# MainBoard.net
KiCad netlist of a schematic drawn in Altium Designer
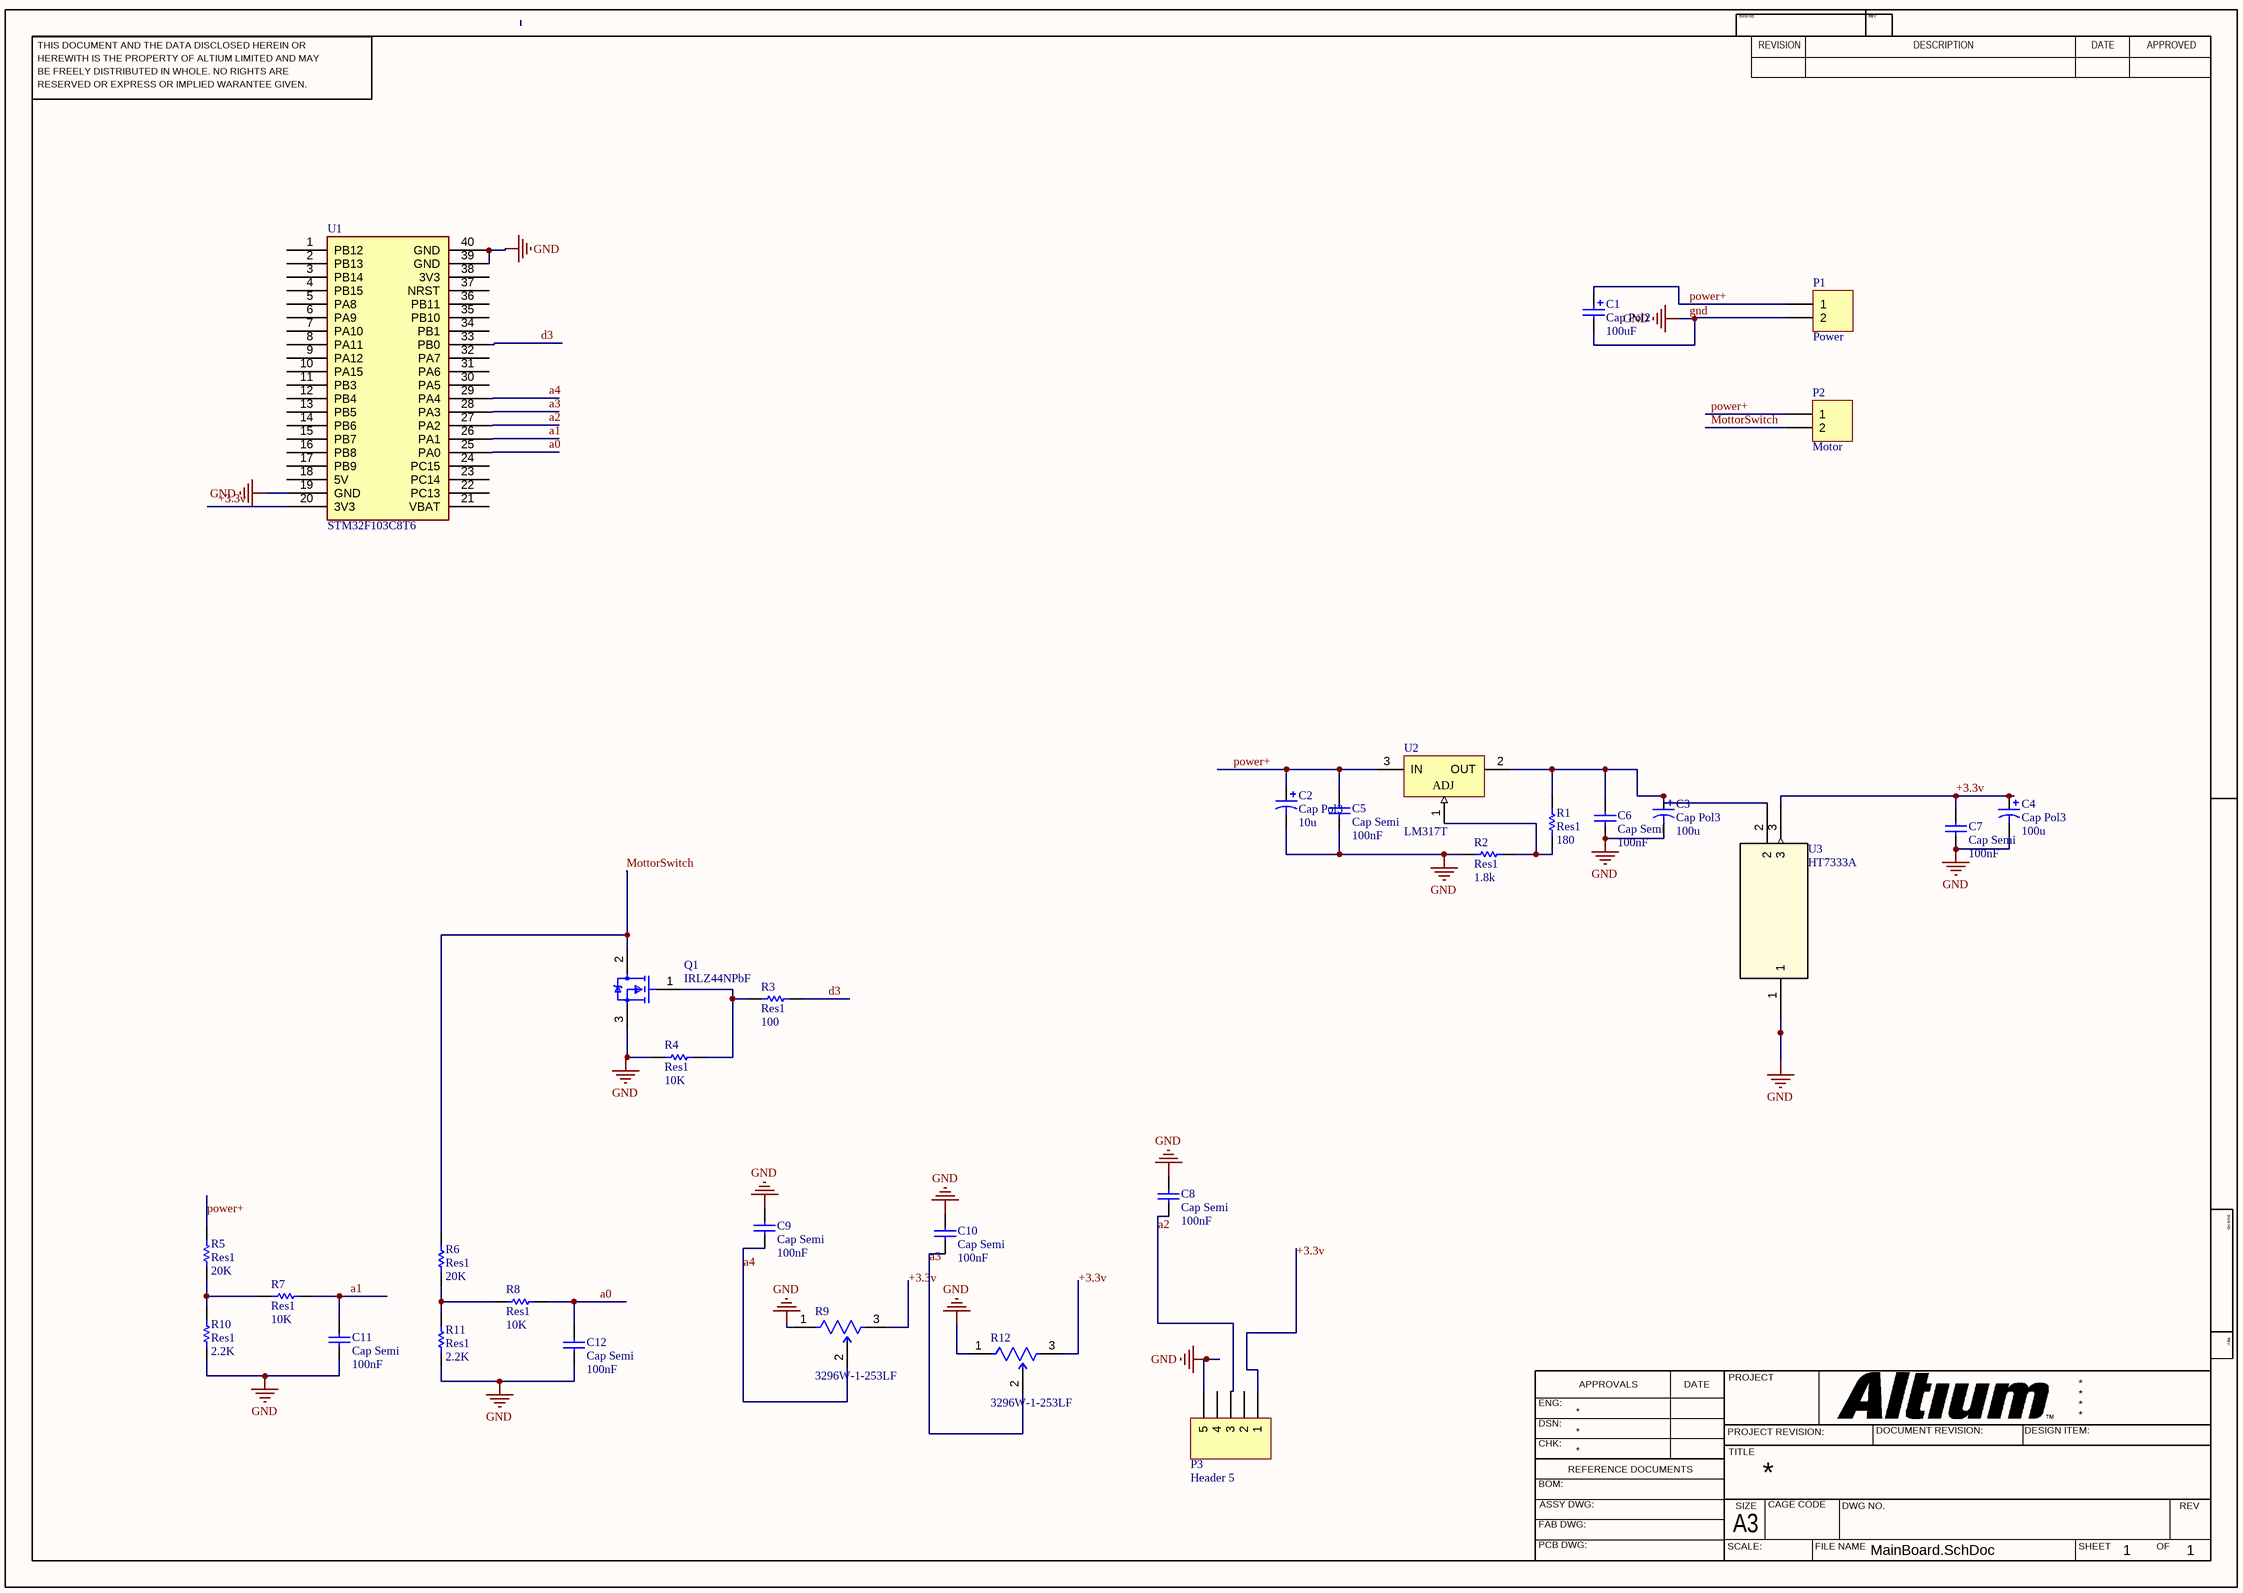
[diagram p0: MainBoard.SchDoc]

(export (version "E")
  (design (tool "Eeschema 10.0.6"))
  (components
    (comp (ref "C1")
      (value "Cap Pol2")
      (footprint "RB5-10.5")
      (description "Polarized Capacitor (Axial)")
      (fields (field (name "ALTIUM_VALUE") "100uF") (field (name "PUBLISHER") "Altium Limited"))
      (libsource (lib "Miscellaneous Devices") (part "Cap Pol2"))
    )
    (comp (ref "C2")
      (value "Cap Pol3")
      (footprint "RAD-0.1")
      (description "Polarized Capacitor (Surface Mount)")
      (fields (field (name "ALTIUM_VALUE") "10u") (field (name "PUBLISHER") "Altium Limited"))
      (libsource (lib "Miscellaneous Devices") (part "Cap Pol3"))
    )
    (comp (ref "C3")
      (value "Cap Pol3")
      (footprint "RAD-0.1")
      (description "Polarized Capacitor (Surface Mount)")
      (fields (field (name "ALTIUM_VALUE") "100u") (field (name "PUBLISHER") "Altium Limited"))
      (libsource (lib "Miscellaneous Devices") (part "Cap Pol3"))
    )
    (comp (ref "C4")
      (value "Cap Pol3")
      (footprint "RAD-0.1")
      (description "Polarized Capacitor (Surface Mount)")
      (fields (field (name "ALTIUM_VALUE") "100u") (field (name "PUBLISHER") "Altium Limited"))
      (libsource (lib "Miscellaneous Devices") (part "Cap Pol3"))
    )
    (comp (ref "C5")
      (value "Cap Semi")
      (footprint "RAD-0.1")
      (description "Capacitor (Semiconductor SIM Model)")
      (fields (field (name "ALTIUM_VALUE") "100nF") (field (name "PUBLISHER") "Altium Limited"))
      (libsource (lib "Miscellaneous Devices") (part "Cap Semi"))
    )
    (comp (ref "C6")
      (value "Cap Semi")
      (footprint "RAD-0.1")
      (description "Capacitor (Semiconductor SIM Model)")
      (fields (field (name "ALTIUM_VALUE") "100nF") (field (name "PUBLISHER") "Altium Limited"))
      (libsource (lib "Miscellaneous Devices") (part "Cap Semi"))
    )
    (comp (ref "C7")
      (value "Cap Semi")
      (footprint "RAD-0.1")
      (description "Capacitor (Semiconductor SIM Model)")
      (fields (field (name "ALTIUM_VALUE") "100nF") (field (name "PUBLISHER") "Altium Limited"))
      (libsource (lib "Miscellaneous Devices") (part "Cap Semi"))
    )
    (comp (ref "C8")
      (value "Cap Semi")
      (footprint "RAD-0.1")
      (description "Capacitor (Semiconductor SIM Model)")
      (fields (field (name "ALTIUM_VALUE") "100nF") (field (name "PUBLISHER") "Altium Limited"))
      (libsource (lib "Miscellaneous Devices") (part "Cap Semi"))
    )
    (comp (ref "C9")
      (value "Cap Semi")
      (footprint "RAD-0.1")
      (description "Capacitor (Semiconductor SIM Model)")
      (fields (field (name "ALTIUM_VALUE") "100nF") (field (name "PUBLISHER") "Altium Limited"))
      (libsource (lib "Miscellaneous Devices") (part "Cap Semi"))
    )
    (comp (ref "C10")
      (value "Cap Semi")
      (footprint "RAD-0.1")
      (description "Capacitor (Semiconductor SIM Model)")
      (fields (field (name "ALTIUM_VALUE") "100nF") (field (name "PUBLISHER") "Altium Limited"))
      (libsource (lib "Miscellaneous Devices") (part "Cap Semi"))
    )
    (comp (ref "C11")
      (value "Cap Semi")
      (footprint "RAD-0.1")
      (description "Capacitor (Semiconductor SIM Model)")
      (fields (field (name "ALTIUM_VALUE") "100nF") (field (name "PUBLISHER") "Altium Limited"))
      (libsource (lib "Miscellaneous Devices") (part "Cap Semi"))
    )
    (comp (ref "C12")
      (value "Cap Semi")
      (footprint "RAD-0.1")
      (description "Capacitor (Semiconductor SIM Model)")
      (fields (field (name "ALTIUM_VALUE") "100nF") (field (name "PUBLISHER") "Altium Limited"))
      (libsource (lib "Miscellaneous Devices") (part "Cap Semi"))
    )
    (comp (ref "P1")
      (value "Power")
      (footprint "HDR1X2")
      (description "Header, 2-Pin")
      (fields (field (name "PUBLISHER") "Altium Limited"))
      (libsource (lib "Miscellaneous Connectors") (part "Header 2"))
    )
    (comp (ref "P2")
      (value "Motor")
      (footprint "HDR1X2")
      (description "Header, 2-Pin")
      (fields (field (name "PUBLISHER") "Altium Limited"))
      (libsource (lib "Miscellaneous Connectors") (part "Header 2"))
    )
    (comp (ref "P3")
      (value "Header 5")
      (footprint "HDR1X5")
      (description "Header, 5-Pin")
      (fields (field (name "PUBLISHER") "Altium Limited"))
      (libsource (lib "Miscellaneous Connectors") (part "Header 5"))
    )
    (comp (ref "Q1")
      (value "IRLZ44NPbF")
      (footprint "FP-PG-TO220-3-MFG")
      (description "MOSFET N-CH 55V 47A TO220AB")
      (libsource (lib "Altium Content Vault") (part "b09f7f152735e370c1ea22a33fa83d6"))
    )
    (comp (ref "R1")
      (value "Res1")
      (footprint "1608[0603]")
      (description "Resistor")
      (fields (field (name "ALTIUM_VALUE") "180") (field (name "PUBLISHER") "Altium Limited"))
      (libsource (lib "Miscellaneous Devices") (part "Res1"))
    )
    (comp (ref "R2")
      (value "Res1")
      (footprint "1608[0603]")
      (description "Resistor")
      (fields (field (name "ALTIUM_VALUE") "1.8k") (field (name "PUBLISHER") "Altium Limited"))
      (libsource (lib "Miscellaneous Devices") (part "Res1"))
    )
    (comp (ref "R3")
      (value "Res1")
      (footprint "1608[0603]")
      (description "Resistor")
      (fields (field (name "ALTIUM_VALUE") "100") (field (name "PUBLISHER") "Altium Limited"))
      (libsource (lib "Miscellaneous Devices") (part "Res1"))
    )
    (comp (ref "R4")
      (value "Res1")
      (footprint "1608[0603]")
      (description "Resistor")
      (fields (field (name "ALTIUM_VALUE") "10K") (field (name "PUBLISHER") "Altium Limited"))
      (libsource (lib "Miscellaneous Devices") (part "Res1"))
    )
    (comp (ref "R5")
      (value "Res1")
      (footprint "1608[0603]")
      (description "Resistor")
      (fields (field (name "ALTIUM_VALUE") "20K") (field (name "PUBLISHER") "Altium Limited"))
      (libsource (lib "Miscellaneous Devices") (part "Res1"))
    )
    (comp (ref "R6")
      (value "Res1")
      (footprint "1608[0603]")
      (description "Resistor")
      (fields (field (name "ALTIUM_VALUE") "20K") (field (name "PUBLISHER") "Altium Limited"))
      (libsource (lib "Miscellaneous Devices") (part "Res1"))
    )
    (comp (ref "R7")
      (value "Res1")
      (footprint "1608[0603]")
      (description "Resistor")
      (fields (field (name "ALTIUM_VALUE") "10K") (field (name "PUBLISHER") "Altium Limited"))
      (libsource (lib "Miscellaneous Devices") (part "Res1"))
    )
    (comp (ref "R8")
      (value "Res1")
      (footprint "1608[0603]")
      (description "Resistor")
      (fields (field (name "ALTIUM_VALUE") "10K") (field (name "PUBLISHER") "Altium Limited"))
      (libsource (lib "Miscellaneous Devices") (part "Res1"))
    )
    (comp (ref "R9")
      (value "3296W-1-253LF")
      (footprint "FP-3296W-MFG")
      (description "TRIMMER 25K OHM 0.5W PC PIN TOP")
      (fields (field (name "TOLERANCE") "10%"))
      (libsource (lib "Altium Content Vault") (part "2dcfd2547301a7d3209a5e99acfd772"))
    )
    (comp (ref "R10")
      (value "Res1")
      (footprint "1608[0603]")
      (description "Resistor")
      (fields (field (name "ALTIUM_VALUE") "2.2K") (field (name "PUBLISHER") "Altium Limited"))
      (libsource (lib "Miscellaneous Devices") (part "Res1"))
    )
    (comp (ref "R11")
      (value "Res1")
      (footprint "1608[0603]")
      (description "Resistor")
      (fields (field (name "ALTIUM_VALUE") "2.2K") (field (name "PUBLISHER") "Altium Limited"))
      (libsource (lib "Miscellaneous Devices") (part "Res1"))
    )
    (comp (ref "R12")
      (value "3296W-1-253LF")
      (footprint "FP-3296W-MFG")
      (description "TRIMMER 25K OHM 0.5W PC PIN TOP")
      (fields (field (name "TOLERANCE") "10%"))
      (libsource (lib "Altium Content Vault") (part "2dcfd2547301a7d3209a5e99acfd772"))
    )
    (comp (ref "U1")
      (value "STM32F103C8T6")
      (footprint "Stm32 BluePill")
      (description "Designed By @Alixahedi")
      (libsource (lib "Stm32 Blue Pill") (part "BluePill"))
    )
    (comp (ref "U2")
      (value "LM317T")
      (footprint "TO-220")
      (description "1.5A, 1.2V to 37V Adjustable Voltage Regulator, 3-Pin TO-220")
      (libsource (lib "Altium Content Vault") (part "PM-REG-117-SIL3"))
    )
    (comp (ref "U3")
      (value "HT7333A")
      (footprint "SOT_7136-1_HLT")
      (description "Description")
      (fields (field (name "COPYRIGHT") "Copyright (C) 2026 Ultra Librarian. All rights reserved."))
      (libsource (lib "HT7333A") (part "HT7333A"))
    )
  )
  (nets
    (net (code "1") (name "/+3.3v") (class "Default")
      (node (ref "C4") (pin "1") (pinfunction "1_1") (pintype "passive"))
      (node (ref "C7") (pin "2") (pinfunction "2_2") (pintype "passive"))
      (node (ref "P3") (pin "1") (pinfunction "1_1") (pintype "passive"))
      (node (ref "R12") (pin "3") (pinfunction "CW_3") (pintype "passive"))
      (node (ref "R9") (pin "3") (pinfunction "CW_3") (pintype "passive"))
      (node (ref "U1") (pin "20") (pinfunction "3V3_20") (pintype "passive"))
      (node (ref "U3") (pin "3") (pinfunction "3_3") (pintype "output"))
    )
    (net (code "2") (name "/MottorSwitch") (class "Default")
      (node (ref "P2") (pin "2") (pinfunction "2_2") (pintype "passive"))
      (node (ref "Q1") (pin "2") (pinfunction "D_2") (pintype "passive"))
      (node (ref "R6") (pin "2") (pinfunction "2_2") (pintype "passive"))
    )
    (net (code "3") (name "/a0") (class "Default")
      (node (ref "C12") (pin "2") (pinfunction "2_2") (pintype "passive"))
      (node (ref "R8") (pin "2") (pinfunction "2_2") (pintype "passive"))
      (node (ref "U1") (pin "25") (pinfunction "PA0_25") (pintype "passive"))
    )
    (net (code "4") (name "/a1") (class "Default")
      (node (ref "C11") (pin "2") (pinfunction "2_2") (pintype "passive"))
      (node (ref "R7") (pin "2") (pinfunction "2_2") (pintype "passive"))
      (node (ref "U1") (pin "26") (pinfunction "PA1_26") (pintype "passive"))
    )
    (net (code "5") (name "/a2") (class "Default")
      (node (ref "C8") (pin "1") (pinfunction "1_1") (pintype "passive"))
      (node (ref "P3") (pin "3") (pinfunction "3_3") (pintype "passive"))
      (node (ref "U1") (pin "27") (pinfunction "PA2_27") (pintype "passive"))
    )
    (net (code "6") (name "/a3") (class "Default")
      (node (ref "C10") (pin "1") (pinfunction "1_1") (pintype "passive"))
      (node (ref "R12") (pin "2") (pinfunction "WIPER_2") (pintype "passive"))
      (node (ref "U1") (pin "28") (pinfunction "PA3_28") (pintype "passive"))
    )
    (net (code "7") (name "/a4") (class "Default")
      (node (ref "C9") (pin "1") (pinfunction "1_1") (pintype "passive"))
      (node (ref "R9") (pin "2") (pinfunction "WIPER_2") (pintype "passive"))
      (node (ref "U1") (pin "29") (pinfunction "PA4_29") (pintype "passive"))
    )
    (net (code "8") (name "/d3") (class "Default")
      (node (ref "R3") (pin "2") (pinfunction "2_2") (pintype "passive"))
      (node (ref "U1") (pin "33") (pinfunction "PB0_33") (pintype "passive"))
    )
    (net (code "9") (name "/power+") (class "Default")
      (node (ref "C1") (pin "1") (pinfunction "1_1") (pintype "passive"))
      (node (ref "C2") (pin "1") (pinfunction "1_1") (pintype "passive"))
      (node (ref "C5") (pin "2") (pinfunction "2_2") (pintype "passive"))
      (node (ref "P1") (pin "1") (pinfunction "1_1") (pintype "passive"))
      (node (ref "P2") (pin "1") (pinfunction "1_1") (pintype "passive"))
      (node (ref "R5") (pin "2") (pinfunction "2_2") (pintype "passive"))
      (node (ref "U2") (pin "3") (pinfunction "IN_3") (pintype "power_in"))
    )
    (net (code "10") (name "GND") (class "Default")
      (node (ref "C1") (pin "2") (pinfunction "2_2") (pintype "passive"))
      (node (ref "C10") (pin "2") (pinfunction "2_2") (pintype "passive"))
      (node (ref "C11") (pin "1") (pinfunction "1_1") (pintype "passive"))
      (node (ref "C12") (pin "1") (pinfunction "1_1") (pintype "passive"))
      (node (ref "C2") (pin "2") (pinfunction "2_2") (pintype "passive"))
      (node (ref "C3") (pin "2") (pinfunction "2_2") (pintype "passive"))
      (node (ref "C4") (pin "2") (pinfunction "2_2") (pintype "passive"))
      (node (ref "C5") (pin "1") (pinfunction "1_1") (pintype "passive"))
      (node (ref "C6") (pin "1") (pinfunction "1_1") (pintype "passive"))
      (node (ref "C7") (pin "1") (pinfunction "1_1") (pintype "passive"))
      (node (ref "C8") (pin "2") (pinfunction "2_2") (pintype "passive"))
      (node (ref "C9") (pin "2") (pinfunction "2_2") (pintype "passive"))
      (node (ref "P1") (pin "2") (pinfunction "2_2") (pintype "passive"))
      (node (ref "P3") (pin "5") (pinfunction "5_5") (pintype "passive"))
      (node (ref "Q1") (pin "3") (pinfunction "S_3") (pintype "passive"))
      (node (ref "R10") (pin "1") (pinfunction "1_1") (pintype "passive"))
      (node (ref "R11") (pin "1") (pinfunction "1_1") (pintype "passive"))
      (node (ref "R12") (pin "1") (pinfunction "CCW_1") (pintype "passive"))
      (node (ref "R2") (pin "1") (pinfunction "1_1") (pintype "passive"))
      (node (ref "R4") (pin "1") (pinfunction "1_1") (pintype "passive"))
      (node (ref "R9") (pin "1") (pinfunction "CCW_1") (pintype "passive"))
      (node (ref "U1") (pin "19") (pinfunction "GND_19") (pintype "passive"))
      (node (ref "U1") (pin "39") (pinfunction "GND_39") (pintype "passive"))
      (node (ref "U1") (pin "40") (pinfunction "GND_40") (pintype "passive"))
      (node (ref "U3") (pin "1") (pinfunction "1_1") (pintype "power_in"))
    )
    (net (code "11") (name "Net-(Q1-G)") (class "Default")
      (node (ref "Q1") (pin "1") (pinfunction "G_1") (pintype "passive"))
      (node (ref "R3") (pin "1") (pinfunction "1_1") (pintype "passive"))
      (node (ref "R4") (pin "2") (pinfunction "2_2") (pintype "passive"))
    )
    (net (code "12") (name "Net-(R10-Pad2)") (class "Default")
      (node (ref "R10") (pin "2") (pinfunction "2_2") (pintype "passive"))
      (node (ref "R5") (pin "1") (pinfunction "1_1") (pintype "passive"))
      (node (ref "R7") (pin "1") (pinfunction "1_1") (pintype "passive"))
    )
    (net (code "13") (name "Net-(R11-Pad2)") (class "Default")
      (node (ref "R11") (pin "2") (pinfunction "2_2") (pintype "passive"))
      (node (ref "R6") (pin "1") (pinfunction "1_1") (pintype "passive"))
      (node (ref "R8") (pin "1") (pinfunction "1_1") (pintype "passive"))
    )
    (net (code "14") (name "Net-(U2-ADJ)") (class "Default")
      (node (ref "R1") (pin "1") (pinfunction "1_1") (pintype "passive"))
      (node (ref "R2") (pin "2") (pinfunction "2_2") (pintype "passive"))
      (node (ref "U2") (pin "1") (pinfunction "ADJ_1") (pintype "input"))
    )
    (net (code "15") (name "Net-(U2-OUT)") (class "Default")
      (node (ref "C3") (pin "1") (pinfunction "1_1") (pintype "passive"))
      (node (ref "C6") (pin "2") (pinfunction "2_2") (pintype "passive"))
      (node (ref "R1") (pin "2") (pinfunction "2_2") (pintype "passive"))
      (node (ref "U2") (pin "2") (pinfunction "OUT_2") (pintype "power_in"))
      (node (ref "U3") (pin "2") (pinfunction "2_2") (pintype "passive"))
    )
    (net (code "16") (name "unconnected-(P3-Pad2)") (class "Default")
      (node (ref "P3") (pin "2") (pinfunction "2_2") (pintype "passive"))
    )
    (net (code "17") (name "unconnected-(P3-Pad4)") (class "Default")
      (node (ref "P3") (pin "4") (pinfunction "4_4") (pintype "passive"))
    )
    (net (code "18") (name "unconnected-(U1-3V3-Pad38)") (class "Default")
      (node (ref "U1") (pin "38") (pinfunction "3V3_38") (pintype "passive"))
    )
    (net (code "19") (name "unconnected-(U1-5V-Pad18)") (class "Default")
      (node (ref "U1") (pin "18") (pinfunction "5V_18") (pintype "passive"))
    )
    (net (code "20") (name "unconnected-(U1-NRST-Pad37)") (class "Default")
      (node (ref "U1") (pin "37") (pinfunction "NRST_37") (pintype "passive"))
    )
    (net (code "21") (name "unconnected-(U1-PA5-Pad30)") (class "Default")
      (node (ref "U1") (pin "30") (pinfunction "PA5_30") (pintype "passive"))
    )
    (net (code "22") (name "unconnected-(U1-PA6-Pad31)") (class "Default")
      (node (ref "U1") (pin "31") (pinfunction "PA6_31") (pintype "passive"))
    )
    (net (code "23") (name "unconnected-(U1-PA7-Pad32)") (class "Default")
      (node (ref "U1") (pin "32") (pinfunction "PA7_32") (pintype "passive"))
    )
    (net (code "24") (name "unconnected-(U1-PA8-Pad5)") (class "Default")
      (node (ref "U1") (pin "5") (pinfunction "PA8_5") (pintype "passive"))
    )
    (net (code "25") (name "unconnected-(U1-PA9-Pad6)") (class "Default")
      (node (ref "U1") (pin "6") (pinfunction "PA9_6") (pintype "passive"))
    )
    (net (code "26") (name "unconnected-(U1-PA10-Pad7)") (class "Default")
      (node (ref "U1") (pin "7") (pinfunction "PA10_7") (pintype "passive"))
    )
    (net (code "27") (name "unconnected-(U1-PA11-Pad8)") (class "Default")
      (node (ref "U1") (pin "8") (pinfunction "PA11_8") (pintype "passive"))
    )
    (net (code "28") (name "unconnected-(U1-PA12-Pad9)") (class "Default")
      (node (ref "U1") (pin "9") (pinfunction "PA12_9") (pintype "passive"))
    )
    (net (code "29") (name "unconnected-(U1-PA15-Pad10)") (class "Default")
      (node (ref "U1") (pin "10") (pinfunction "PA15_10") (pintype "passive"))
    )
    (net (code "30") (name "unconnected-(U1-PB1-Pad34)") (class "Default")
      (node (ref "U1") (pin "34") (pinfunction "PB1_34") (pintype "passive"))
    )
    (net (code "31") (name "unconnected-(U1-PB3-Pad11)") (class "Default")
      (node (ref "U1") (pin "11") (pinfunction "PB3_11") (pintype "passive"))
    )
    (net (code "32") (name "unconnected-(U1-PB4-Pad12)") (class "Default")
      (node (ref "U1") (pin "12") (pinfunction "PB4_12") (pintype "passive"))
    )
    (net (code "33") (name "unconnected-(U1-PB5-Pad13)") (class "Default")
      (node (ref "U1") (pin "13") (pinfunction "PB5_13") (pintype "passive"))
    )
    (net (code "34") (name "unconnected-(U1-PB6-Pad14)") (class "Default")
      (node (ref "U1") (pin "14") (pinfunction "PB6_14") (pintype "passive"))
    )
    (net (code "35") (name "unconnected-(U1-PB7-Pad15)") (class "Default")
      (node (ref "U1") (pin "15") (pinfunction "PB7_15") (pintype "passive"))
    )
    (net (code "36") (name "unconnected-(U1-PB8-Pad16)") (class "Default")
      (node (ref "U1") (pin "16") (pinfunction "PB8_16") (pintype "passive"))
    )
    (net (code "37") (name "unconnected-(U1-PB9-Pad17)") (class "Default")
      (node (ref "U1") (pin "17") (pinfunction "PB9_17") (pintype "passive"))
    )
    (net (code "38") (name "unconnected-(U1-PB10-Pad35)") (class "Default")
      (node (ref "U1") (pin "35") (pinfunction "PB10_35") (pintype "passive"))
    )
    (net (code "39") (name "unconnected-(U1-PB11-Pad36)") (class "Default")
      (node (ref "U1") (pin "36") (pinfunction "PB11_36") (pintype "passive"))
    )
    (net (code "40") (name "unconnected-(U1-PB12-Pad1)") (class "Default")
      (node (ref "U1") (pin "1") (pinfunction "PB12_1") (pintype "passive"))
    )
    (net (code "41") (name "unconnected-(U1-PB13-Pad2)") (class "Default")
      (node (ref "U1") (pin "2") (pinfunction "PB13_2") (pintype "passive"))
    )
    (net (code "42") (name "unconnected-(U1-PB14-Pad3)") (class "Default")
      (node (ref "U1") (pin "3") (pinfunction "PB14_3") (pintype "passive"))
    )
    (net (code "43") (name "unconnected-(U1-PB15-Pad4)") (class "Default")
      (node (ref "U1") (pin "4") (pinfunction "PB15_4") (pintype "passive"))
    )
    (net (code "44") (name "unconnected-(U1-PC13-Pad22)") (class "Default")
      (node (ref "U1") (pin "22") (pinfunction "PC13_22") (pintype "passive"))
    )
    (net (code "45") (name "unconnected-(U1-PC14-Pad23)") (class "Default")
      (node (ref "U1") (pin "23") (pinfunction "PC14_23") (pintype "passive"))
    )
    (net (code "46") (name "unconnected-(U1-PC15-Pad24)") (class "Default")
      (node (ref "U1") (pin "24") (pinfunction "PC15_24") (pintype "passive"))
    )
    (net (code "47") (name "unconnected-(U1-VBAT-Pad21)") (class "Default")
      (node (ref "U1") (pin "21") (pinfunction "VBAT_21") (pintype "passive"))
    )
  )
)
